# avoccado-nora2-test-jig-panel-single.net
KiCad netlist of a schematic drawn in EAGLE
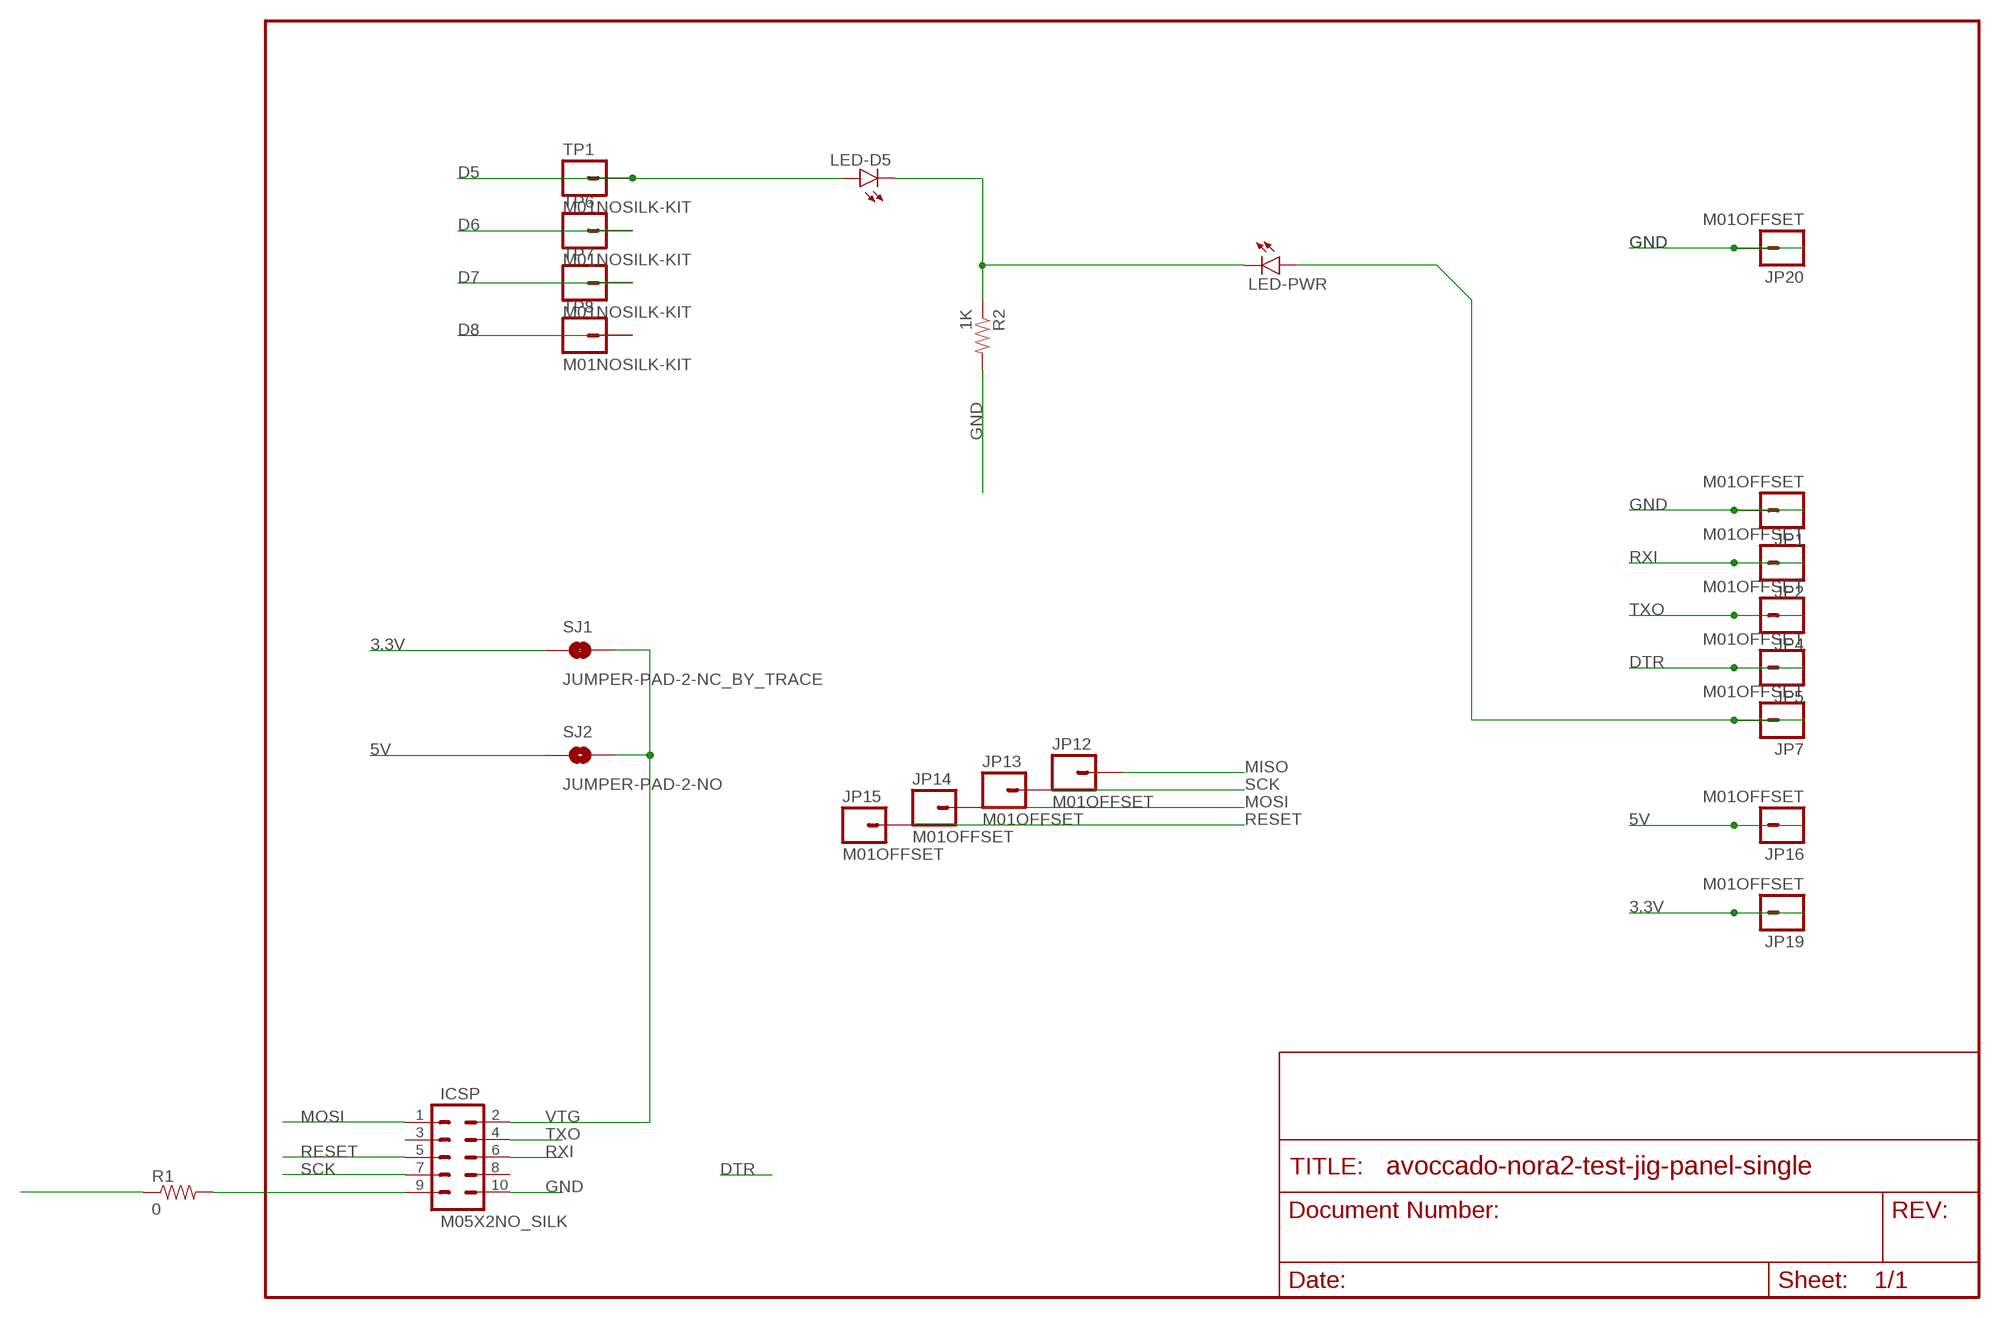
[diagram p0: schematic, sheet 1]

(export (version "E")
  (design (tool "Eeschema 10.0.6"))
  (components
    (comp (ref "ICSP")
      (value "M05X2NO_SILK")
      (footprint "eagle-import:2X5_NOSILK")
      (libsource (lib "eagle-import") (part "M05X2NO_SILK"))
    )
    (comp (ref "JP1")
      (value "M01OFFSET")
      (footprint "eagle-import:1X01_OFFSET")
      (libsource (lib "eagle-import") (part "M01OFFSET"))
    )
    (comp (ref "JP2")
      (value "M01OFFSET")
      (footprint "eagle-import:1X01_OFFSET")
      (libsource (lib "eagle-import") (part "M01OFFSET"))
    )
    (comp (ref "JP4")
      (value "M01OFFSET")
      (footprint "eagle-import:1X01_OFFSET")
      (libsource (lib "eagle-import") (part "M01OFFSET"))
    )
    (comp (ref "JP5")
      (value "M01OFFSET")
      (footprint "eagle-import:1X01_OFFSET")
      (libsource (lib "eagle-import") (part "M01OFFSET"))
    )
    (comp (ref "JP7")
      (value "M01OFFSET")
      (footprint "eagle-import:1X01_OFFSET")
      (libsource (lib "eagle-import") (part "M01OFFSET"))
    )
    (comp (ref "JP12")
      (value "M01OFFSET")
      (footprint "eagle-import:1X01_OFFSET")
      (libsource (lib "eagle-import") (part "M01OFFSET"))
    )
    (comp (ref "JP13")
      (value "M01OFFSET")
      (footprint "eagle-import:1X01_OFFSET")
      (libsource (lib "eagle-import") (part "M01OFFSET"))
    )
    (comp (ref "JP14")
      (value "M01OFFSET")
      (footprint "eagle-import:1X01_OFFSET")
      (libsource (lib "eagle-import") (part "M01OFFSET"))
    )
    (comp (ref "JP15")
      (value "M01OFFSET")
      (footprint "eagle-import:1X01_OFFSET")
      (libsource (lib "eagle-import") (part "M01OFFSET"))
    )
    (comp (ref "JP16")
      (value "M01OFFSET")
      (footprint "eagle-import:1X01_OFFSET")
      (libsource (lib "eagle-import") (part "M01OFFSET"))
    )
    (comp (ref "JP19")
      (value "M01OFFSET")
      (footprint "eagle-import:1X01_OFFSET")
      (libsource (lib "eagle-import") (part "M01OFFSET"))
    )
    (comp (ref "JP20")
      (value "M01OFFSET")
      (footprint "eagle-import:1X01_OFFSET")
      (libsource (lib "eagle-import") (part "M01OFFSET"))
    )
    (comp (ref "LED-D5")
      (value "LED0603")
      (footprint "eagle-import:LED-0603")
      (libsource (lib "eagle-import") (part "LED0603"))
    )
    (comp (ref "LED-PWR")
      (value "LED0603")
      (footprint "eagle-import:LED-0603")
      (libsource (lib "eagle-import") (part "LED0603"))
    )
    (comp (ref "R1")
      (value "0")
      (footprint "eagle-import:1206")
      (libsource (lib "eagle-import") (part "RESISTOR1206"))
    )
    (comp (ref "R2")
      (value "1K")
      (footprint "eagle-import:0603-RES")
      (libsource (lib "eagle-import") (part "RESISTOR0603"))
    )
    (comp (ref "SJ1")
      (value "JUMPER-PAD-2-NC_BY_TRACE")
      (footprint "eagle-import:PAD-JUMPER-2-NC_BY_TRACE_YES_SILK")
      (libsource (lib "eagle-import") (part "JUMPER-PAD-2-NC_BY_TRACE"))
    )
    (comp (ref "SJ2")
      (value "JUMPER-PAD-2-NO")
      (footprint "eagle-import:PAD-JUMPER-2-NO_NO_SILK")
      (libsource (lib "eagle-import") (part "JUMPER-PAD-2-NO"))
    )
    (comp (ref "TP1")
      (value "M01NOSILK-KIT")
      (footprint "eagle-import:1X01NS-KIT")
      (libsource (lib "eagle-import") (part "M01NOSILK-KIT"))
    )
    (comp (ref "TP6")
      (value "M01NOSILK-KIT")
      (footprint "eagle-import:1X01NS-KIT")
      (libsource (lib "eagle-import") (part "M01NOSILK-KIT"))
    )
    (comp (ref "TP7")
      (value "M01NOSILK-KIT")
      (footprint "eagle-import:1X01NS-KIT")
      (libsource (lib "eagle-import") (part "M01NOSILK-KIT"))
    )
    (comp (ref "TP8")
      (value "M01NOSILK-KIT")
      (footprint "eagle-import:1X01NS-KIT")
      (libsource (lib "eagle-import") (part "M01NOSILK-KIT"))
    )
  )
  (nets
    (net (code "1") (name "/3.3V") (class "Default")
      (node (ref "JP19") (pin "1") (pinfunction "1_1") (pintype "passive"))
      (node (ref "SJ1") (pin "1") (pinfunction "1_1") (pintype "passive"))
    )
    (net (code "2") (name "/5V") (class "Default")
      (node (ref "JP16") (pin "1") (pinfunction "1_1") (pintype "passive"))
      (node (ref "SJ2") (pin "1") (pinfunction "1_1") (pintype "passive"))
    )
    (net (code "3") (name "/D5") (class "Default")
      (node (ref "LED-D5") (pin "A") (pinfunction "A_A") (pintype "passive"))
      (node (ref "TP1") (pin "1") (pinfunction "1_1") (pintype "passive"))
    )
    (net (code "4") (name "/D6") (class "Default")
      (node (ref "TP6") (pin "1") (pinfunction "1_1") (pintype "passive"))
    )
    (net (code "5") (name "/D7") (class "Default")
      (node (ref "TP7") (pin "1") (pinfunction "1_1") (pintype "passive"))
    )
    (net (code "6") (name "/D8") (class "Default")
      (node (ref "TP8") (pin "1") (pinfunction "1_1") (pintype "passive"))
    )
    (net (code "7") (name "/DTR") (class "Default")
      (node (ref "JP5") (pin "1") (pinfunction "1_1") (pintype "passive"))
    )
    (net (code "8") (name "/GND") (class "Default")
      (node (ref "ICSP") (pin "10") (pinfunction "10_10") (pintype "passive"))
      (node (ref "JP1") (pin "1") (pinfunction "1_1") (pintype "passive"))
      (node (ref "JP20") (pin "1") (pinfunction "1_1") (pintype "passive"))
      (node (ref "R2") (pin "2") (pinfunction "2_2") (pintype "passive"))
    )
    (net (code "9") (name "/MISO") (class "Default")
      (node (ref "JP12") (pin "1") (pinfunction "1_1") (pintype "passive"))
      (node (ref "R1") (pin "1") (pinfunction "1_1") (pintype "passive"))
    )
    (net (code "10") (name "/MOSI") (class "Default")
      (node (ref "ICSP") (pin "1") (pinfunction "1_1") (pintype "passive"))
      (node (ref "JP14") (pin "1") (pinfunction "1_1") (pintype "passive"))
    )
    (net (code "11") (name "/RESET") (class "Default")
      (node (ref "ICSP") (pin "5") (pinfunction "5_5") (pintype "passive"))
      (node (ref "JP15") (pin "1") (pinfunction "1_1") (pintype "passive"))
    )
    (net (code "12") (name "/RXI") (class "Default")
      (node (ref "ICSP") (pin "6") (pinfunction "6_6") (pintype "passive"))
      (node (ref "JP2") (pin "1") (pinfunction "1_1") (pintype "passive"))
    )
    (net (code "13") (name "/SCK") (class "Default")
      (node (ref "ICSP") (pin "7") (pinfunction "7_7") (pintype "passive"))
      (node (ref "JP13") (pin "1") (pinfunction "1_1") (pintype "passive"))
    )
    (net (code "14") (name "/TXO") (class "Default")
      (node (ref "ICSP") (pin "4") (pinfunction "4_4") (pintype "passive"))
      (node (ref "JP4") (pin "1") (pinfunction "1_1") (pintype "passive"))
    )
    (net (code "15") (name "/VTG") (class "Default")
      (node (ref "ICSP") (pin "2") (pinfunction "2_2") (pintype "passive"))
      (node (ref "SJ1") (pin "2") (pinfunction "2_2") (pintype "passive"))
      (node (ref "SJ2") (pin "2") (pinfunction "2_2") (pintype "passive"))
    )
    (net (code "16") (name "Net-(ICSP-Pad9)") (class "Default")
      (node (ref "ICSP") (pin "9") (pinfunction "9_9") (pintype "passive"))
      (node (ref "R1") (pin "2") (pinfunction "2_2") (pintype "passive"))
    )
    (net (code "17") (name "Net-(JP7-Pad1)") (class "Default")
      (node (ref "JP7") (pin "1") (pinfunction "1_1") (pintype "passive"))
      (node (ref "LED-PWR") (pin "A") (pinfunction "A_A") (pintype "passive"))
    )
    (net (code "18") (name "Net-(LED-D5-PadC)") (class "Default")
      (node (ref "LED-D5") (pin "C") (pinfunction "C_C") (pintype "passive"))
      (node (ref "LED-PWR") (pin "C") (pinfunction "C_C") (pintype "passive"))
      (node (ref "R2") (pin "1") (pinfunction "1_1") (pintype "passive"))
    )
    (net (code "19") (name "unconnected-(ICSP-Pad3)") (class "Default")
      (node (ref "ICSP") (pin "3") (pinfunction "3_3") (pintype "passive"))
    )
    (net (code "20") (name "unconnected-(ICSP-Pad8)") (class "Default")
      (node (ref "ICSP") (pin "8") (pinfunction "8_8") (pintype "passive"))
    )
  )
)
